# REFCLK.net
KiCad netlist of a schematic drawn in Altium Designer
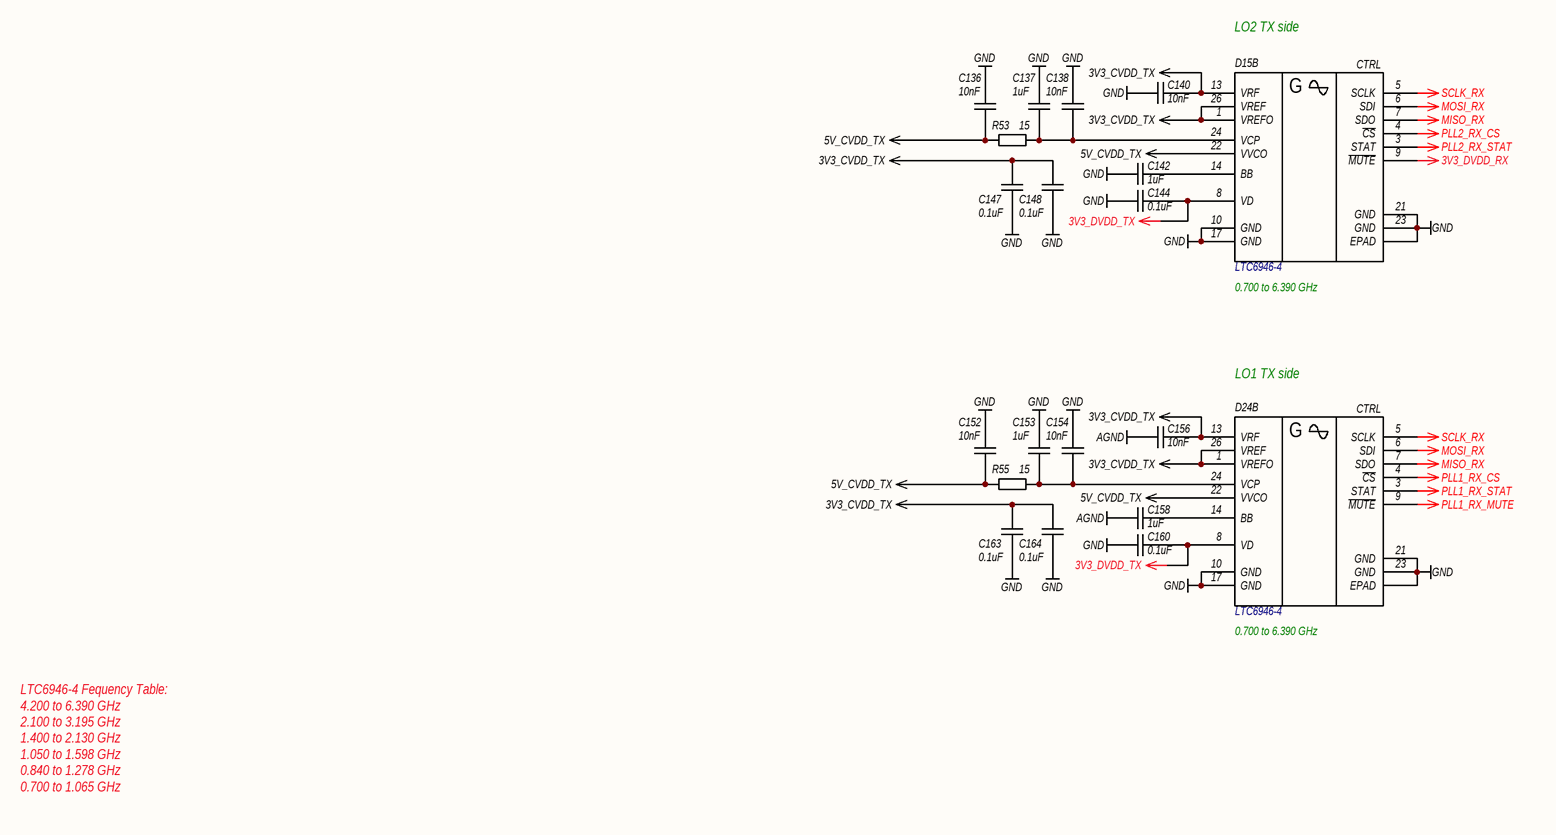
[diagram p0: REFCLK.SchDoc]

(export (version "E")
  (design (tool "Eeschema 10.0.6"))
  (components
    (comp (ref "C136")
      (value "10nF")
      (footprint "C0402")
      (description "SMD Capacitor")
      (fields (field (name "MANUFACTURER") "Murata") (field (name "TOLERANCE") "10%"))
      (libsource (lib "Kintex_SDR") (part "CAP"))
    )
    (comp (ref "C137")
      (value "1uF")
      (footprint "C0805")
      (description "SMD Capacitor")
      (fields (field (name "MANUFACTURER") "Murata") (field (name "TOLERANCE") "10%"))
      (libsource (lib "Kintex_SDR") (part "CAP"))
    )
    (comp (ref "C138")
      (value "10nF")
      (footprint "C0402")
      (description "SMD Capacitor")
      (fields (field (name "MANUFACTURER") "Murata") (field (name "TOLERANCE") "10%"))
      (libsource (lib "Kintex_SDR") (part "CAP"))
    )
    (comp (ref "C140")
      (value "10nF")
      (footprint "C0402")
      (description "SMD Capacitor")
      (fields (field (name "MANUFACTURER") "Murata") (field (name "TOLERANCE") "10%"))
      (libsource (lib "Kintex_SDR") (part "CAP"))
    )
    (comp (ref "C142")
      (value "1uF")
      (footprint "C0805")
      (description "SMD Capacitor")
      (fields (field (name "MANUFACTURER") "Murata") (field (name "TOLERANCE") "10%"))
      (libsource (lib "Kintex_SDR") (part "CAP"))
    )
    (comp (ref "C144")
      (value "0.1uF")
      (footprint "C0402")
      (description "SMD Capacitor")
      (fields (field (name "MANUFACTURER") "Murata") (field (name "TOLERANCE") "10%"))
      (libsource (lib "Kintex_SDR") (part "CAP"))
    )
    (comp (ref "C147")
      (value "0.1uF")
      (footprint "C0402")
      (description "SMD Capacitor")
      (fields (field (name "MANUFACTURER") "Murata") (field (name "TOLERANCE") "10%"))
      (libsource (lib "Kintex_SDR") (part "CAP"))
    )
    (comp (ref "C148")
      (value "0.1uF")
      (footprint "C0402")
      (description "SMD Capacitor")
      (fields (field (name "MANUFACTURER") "Murata") (field (name "TOLERANCE") "10%"))
      (libsource (lib "Kintex_SDR") (part "CAP"))
    )
    (comp (ref "C152")
      (value "10nF")
      (footprint "C0402")
      (description "SMD Capacitor")
      (fields (field (name "MANUFACTURER") "Murata") (field (name "TOLERANCE") "10%"))
      (libsource (lib "Kintex_SDR") (part "CAP"))
    )
    (comp (ref "C153")
      (value "1uF")
      (footprint "C0805")
      (description "SMD Capacitor")
      (fields (field (name "MANUFACTURER") "Murata") (field (name "TOLERANCE") "10%"))
      (libsource (lib "Kintex_SDR") (part "CAP"))
    )
    (comp (ref "C154")
      (value "10nF")
      (footprint "C0402")
      (description "SMD Capacitor")
      (fields (field (name "MANUFACTURER") "Murata") (field (name "TOLERANCE") "10%"))
      (libsource (lib "Kintex_SDR") (part "CAP"))
    )
    (comp (ref "C156")
      (value "10nF")
      (footprint "C0402")
      (description "SMD Capacitor")
      (fields (field (name "MANUFACTURER") "Murata") (field (name "TOLERANCE") "10%"))
      (libsource (lib "Kintex_SDR") (part "CAP"))
    )
    (comp (ref "C158")
      (value "1uF")
      (footprint "C0805")
      (description "SMD Capacitor")
      (fields (field (name "MANUFACTURER") "Murata") (field (name "TOLERANCE") "10%"))
      (libsource (lib "Kintex_SDR") (part "CAP"))
    )
    (comp (ref "C160")
      (value "0.1uF")
      (footprint "C0402")
      (description "SMD Capacitor")
      (fields (field (name "MANUFACTURER") "Murata") (field (name "TOLERANCE") "10%"))
      (libsource (lib "Kintex_SDR") (part "CAP"))
    )
    (comp (ref "C163")
      (value "0.1uF")
      (footprint "C0402")
      (description "SMD Capacitor")
      (fields (field (name "MANUFACTURER") "Murata") (field (name "TOLERANCE") "10%"))
      (libsource (lib "Kintex_SDR") (part "CAP"))
    )
    (comp (ref "C164")
      (value "0.1uF")
      (footprint "C0402")
      (description "SMD Capacitor")
      (fields (field (name "MANUFACTURER") "Murata") (field (name "TOLERANCE") "10%"))
      (libsource (lib "Kintex_SDR") (part "CAP"))
    )
    (comp (ref "D15")
      (value "LTC6946")
      (footprint "QFN-28")
      (description "The LTC®6946 is a high performance, low noise, 6.39GHz  phase-locked loop (PLL)")
      (fields
        (field (name "MANUFACTURER") "Linear Technology")
        (field (name "VOLTAGE") "3.15 V ~ 5.25 V")
        (field (name "NAME") "LTC6946-4")
        (field (name "FREQUENCY RANGE") "0.700 to 6.390 GHz")
      )
      (libsource (lib "DBLib") (part "LTC6946"))
    )
    (comp (ref "D24")
      (value "LTC6946")
      (footprint "QFN-28")
      (description "The LTC®6946 is a high performance, low noise, 6.39GHz  phase-locked loop (PLL)")
      (fields
        (field (name "MANUFACTURER") "Linear Technology")
        (field (name "VOLTAGE") "3.15 V ~ 5.25 V")
        (field (name "NAME") "LTC6946-4")
        (field (name "FREQUENCY RANGE") "0.700 to 6.390 GHz")
      )
      (libsource (lib "DBLib") (part "LTC6946"))
    )
    (comp (ref "R53")
      (value "15")
      (footprint "R0603")
      (description "SMD Resistor")
      (fields (field (name "POWER") "0.1 Wt") (field (name "TOLERANCE") "1%"))
      (libsource (lib "Kintex_SDR") (part "RES"))
    )
    (comp (ref "R55")
      (value "15")
      (footprint "R0603")
      (description "SMD Resistor")
      (fields (field (name "POWER") "0.1 Wt") (field (name "TOLERANCE") "1%"))
      (libsource (lib "Kintex_SDR") (part "RES"))
    )
  )
  (nets
    (net (code "1") (name "3V3_CVDD_TX") (class "Default")
      (node (ref "C140") (pin "1") (pinfunction "1_1") (pintype "passive"))
      (node (ref "C147") (pin "2") (pinfunction "2_2") (pintype "passive"))
      (node (ref "C148") (pin "2") (pinfunction "2_2") (pintype "passive"))
      (node (ref "C156") (pin "1") (pinfunction "1_1") (pintype "passive"))
      (node (ref "C163") (pin "2") (pinfunction "2_2") (pintype "passive"))
      (node (ref "C164") (pin "2") (pinfunction "2_2") (pintype "passive"))
      (node (ref "D15") (pin "1") (pinfunction "VREFO_1") (pintype "passive"))
      (node (ref "D15") (pin "13") (pinfunction "VRF_13") (pintype "passive"))
      (node (ref "D15") (pin "26") (pinfunction "VREF_26") (pintype "passive"))
      (node (ref "D24") (pin "1") (pinfunction "VREFO_1") (pintype "passive"))
      (node (ref "D24") (pin "13") (pinfunction "VRF_13") (pintype "passive"))
      (node (ref "D24") (pin "26") (pinfunction "VREF_26") (pintype "passive"))
    )
    (net (code "2") (name "3V3_DVDD_RX") (class "Default")
      (node (ref "D15") (pin "9") (pinfunction "~{MUTE}_9") (pintype "passive"))
    )
    (net (code "3") (name "3V3_DVDD_TX") (class "Default")
      (node (ref "C144") (pin "2") (pinfunction "2_2") (pintype "passive"))
      (node (ref "C160") (pin "2") (pinfunction "2_2") (pintype "passive"))
      (node (ref "D15") (pin "8") (pinfunction "VD_8") (pintype "passive"))
      (node (ref "D24") (pin "8") (pinfunction "VD_8") (pintype "passive"))
    )
    (net (code "4") (name "5V_CVDD_TX") (class "Default")
      (node (ref "C136") (pin "2") (pinfunction "2_2") (pintype "passive"))
      (node (ref "C152") (pin "2") (pinfunction "2_2") (pintype "passive"))
      (node (ref "D15") (pin "22") (pinfunction "VVCO_22") (pintype "passive"))
      (node (ref "D24") (pin "22") (pinfunction "VVCO_22") (pintype "passive"))
      (node (ref "R53") (pin "2") (pinfunction "2_2") (pintype "passive"))
      (node (ref "R55") (pin "2") (pinfunction "2_2") (pintype "passive"))
    )
    (net (code "5") (name "AGND") (class "Default")
      (node (ref "C156") (pin "2") (pinfunction "2_2") (pintype "passive"))
      (node (ref "C158") (pin "2") (pinfunction "2_2") (pintype "passive"))
    )
    (net (code "6") (name "GND") (class "Default")
      (node (ref "C136") (pin "1") (pinfunction "1_1") (pintype "passive"))
      (node (ref "C137") (pin "1") (pinfunction "1_1") (pintype "passive"))
      (node (ref "C138") (pin "1") (pinfunction "1_1") (pintype "passive"))
      (node (ref "C140") (pin "2") (pinfunction "2_2") (pintype "passive"))
      (node (ref "C142") (pin "2") (pinfunction "2_2") (pintype "passive"))
      (node (ref "C144") (pin "1") (pinfunction "1_1") (pintype "passive"))
      (node (ref "C147") (pin "1") (pinfunction "1_1") (pintype "passive"))
      (node (ref "C148") (pin "1") (pinfunction "1_1") (pintype "passive"))
      (node (ref "C152") (pin "1") (pinfunction "1_1") (pintype "passive"))
      (node (ref "C153") (pin "1") (pinfunction "1_1") (pintype "passive"))
      (node (ref "C154") (pin "1") (pinfunction "1_1") (pintype "passive"))
      (node (ref "C160") (pin "1") (pinfunction "1_1") (pintype "passive"))
      (node (ref "C163") (pin "1") (pinfunction "1_1") (pintype "passive"))
      (node (ref "C164") (pin "1") (pinfunction "1_1") (pintype "passive"))
      (node (ref "D15") (pin "10") (pinfunction "GND_10") (pintype "passive"))
      (node (ref "D15") (pin "17") (pinfunction "GND_17") (pintype "passive"))
      (node (ref "D15") (pin "21") (pinfunction "GND_21") (pintype "passive"))
      (node (ref "D15") (pin "23") (pinfunction "GND_23") (pintype "passive"))
      (node (ref "D15") (pin "29") (pinfunction "EPAD_29") (pintype "passive"))
      (node (ref "D24") (pin "10") (pinfunction "GND_10") (pintype "passive"))
      (node (ref "D24") (pin "17") (pinfunction "GND_17") (pintype "passive"))
      (node (ref "D24") (pin "21") (pinfunction "GND_21") (pintype "passive"))
      (node (ref "D24") (pin "23") (pinfunction "GND_23") (pintype "passive"))
      (node (ref "D24") (pin "29") (pinfunction "EPAD_29") (pintype "passive"))
    )
    (net (code "7") (name "MISO_RX") (class "Default")
      (node (ref "D15") (pin "7") (pinfunction "SDO_7") (pintype "passive"))
      (node (ref "D24") (pin "7") (pinfunction "SDO_7") (pintype "passive"))
    )
    (net (code "8") (name "MOSI_RX") (class "Default")
      (node (ref "D15") (pin "6") (pinfunction "SDI_6") (pintype "passive"))
      (node (ref "D24") (pin "6") (pinfunction "SDI_6") (pintype "passive"))
    )
    (net (code "9") (name "Net-(D15B-BB)") (class "Default")
      (node (ref "C142") (pin "1") (pinfunction "1_1") (pintype "passive"))
      (node (ref "D15") (pin "14") (pinfunction "BB_14") (pintype "passive"))
    )
    (net (code "10") (name "Net-(D15B-VCP)") (class "Default")
      (node (ref "C137") (pin "2") (pinfunction "2_2") (pintype "passive"))
      (node (ref "C138") (pin "2") (pinfunction "2_2") (pintype "passive"))
      (node (ref "D15") (pin "24") (pinfunction "VCP_24") (pintype "passive"))
      (node (ref "R53") (pin "1") (pinfunction "1_1") (pintype "passive"))
    )
    (net (code "11") (name "Net-(D24B-BB)") (class "Default")
      (node (ref "C158") (pin "1") (pinfunction "1_1") (pintype "passive"))
      (node (ref "D24") (pin "14") (pinfunction "BB_14") (pintype "passive"))
    )
    (net (code "12") (name "Net-(D24B-VCP)") (class "Default")
      (node (ref "C153") (pin "2") (pinfunction "2_2") (pintype "passive"))
      (node (ref "C154") (pin "2") (pinfunction "2_2") (pintype "passive"))
      (node (ref "D24") (pin "24") (pinfunction "VCP_24") (pintype "passive"))
      (node (ref "R55") (pin "1") (pinfunction "1_1") (pintype "passive"))
    )
    (net (code "13") (name "PLL1_RX_CS") (class "Default")
      (node (ref "D24") (pin "4") (pinfunction "~{CS}_4") (pintype "passive"))
    )
    (net (code "14") (name "PLL1_RX_MUTE") (class "Default")
      (node (ref "D24") (pin "9") (pinfunction "~{MUTE}_9") (pintype "passive"))
    )
    (net (code "15") (name "PLL1_RX_STAT") (class "Default")
      (node (ref "D24") (pin "3") (pinfunction "STAT_3") (pintype "passive"))
    )
    (net (code "16") (name "PLL2_RX_CS") (class "Default")
      (node (ref "D15") (pin "4") (pinfunction "~{CS}_4") (pintype "passive"))
    )
    (net (code "17") (name "PLL2_RX_STAT") (class "Default")
      (node (ref "D15") (pin "3") (pinfunction "STAT_3") (pintype "passive"))
    )
    (net (code "18") (name "SCLK_RX") (class "Default")
      (node (ref "D15") (pin "5") (pinfunction "SCLK_5") (pintype "passive"))
      (node (ref "D24") (pin "5") (pinfunction "SCLK_5") (pintype "passive"))
    )
  )
)
